# Startgate_Controller-Daughterboard.net
KiCad netlist of a schematic drawn in EAGLE
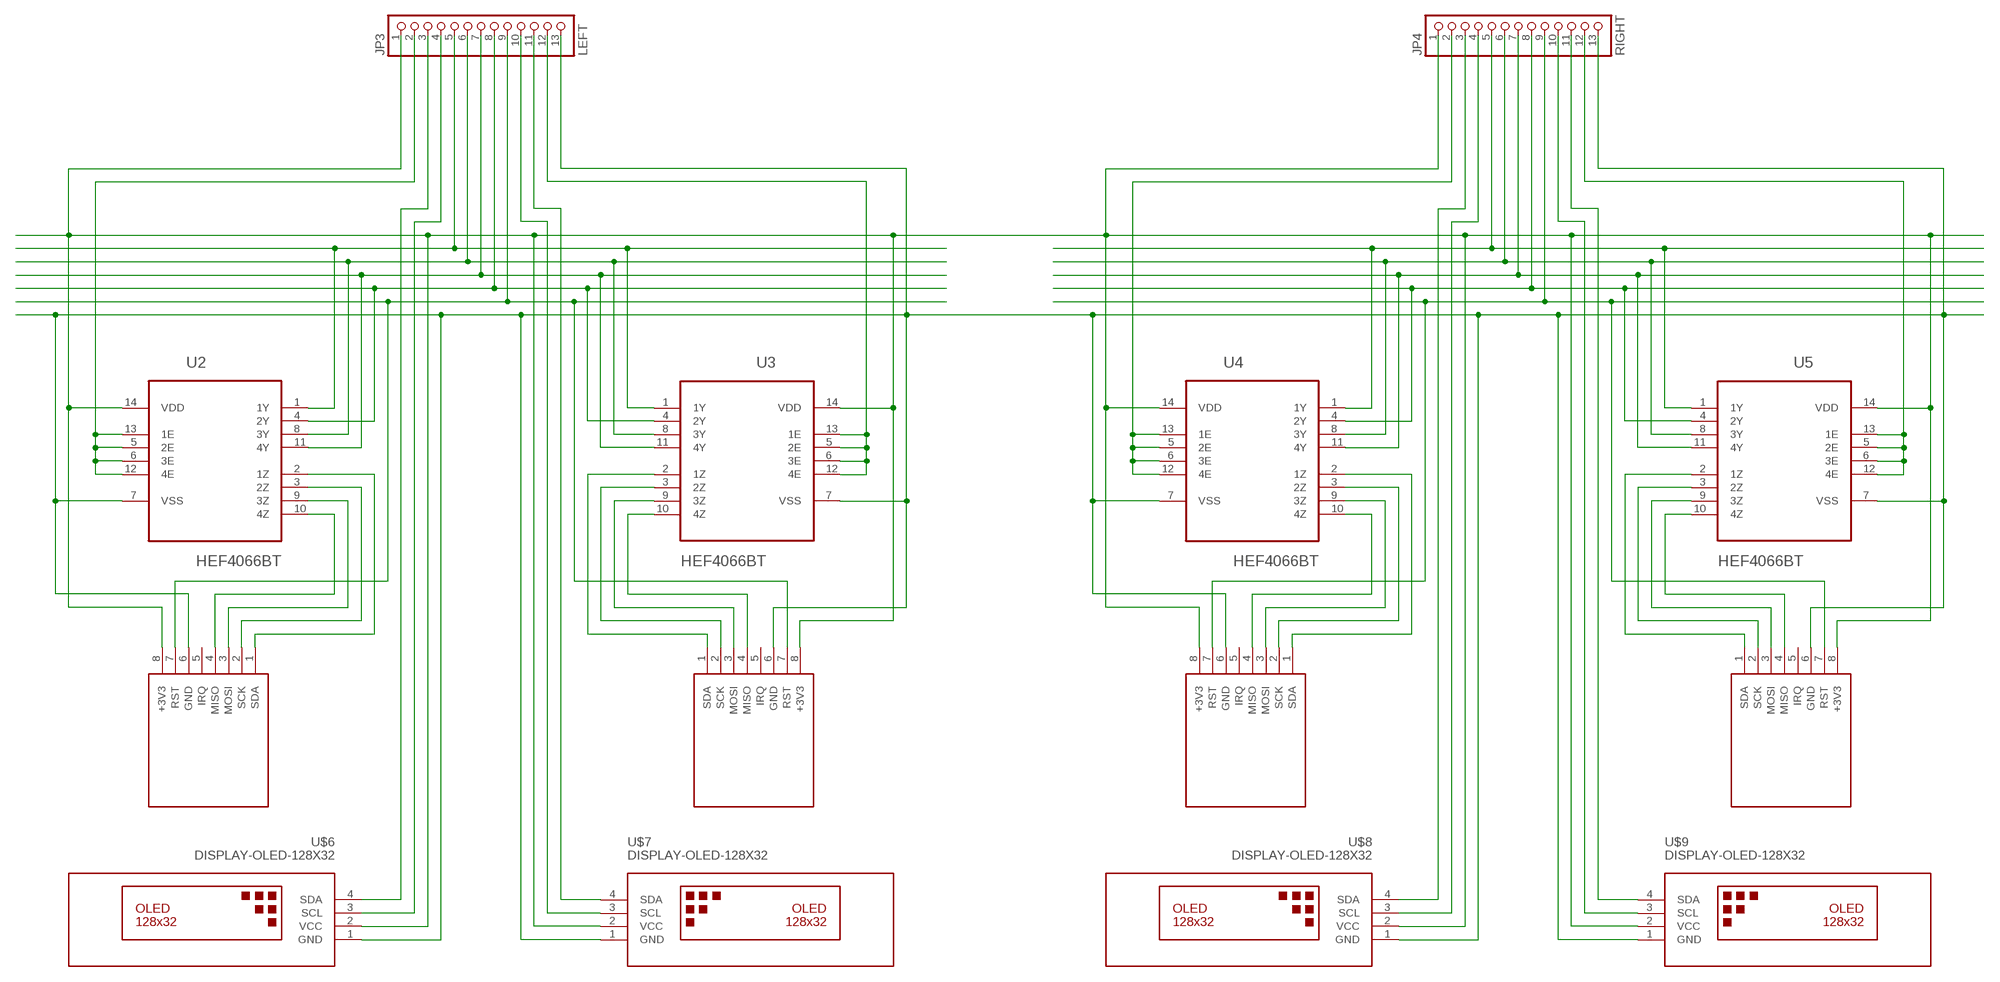
[diagram p0: schematic, sheet 1]

(export (version "E")
  (design (tool "Eeschema 10.0.6"))
  (components
    (comp (ref "JP3")
      (value "LEFT")
      (footprint "eagle-import:1X13")
      (libsource (lib "eagle-import") (part "PINHD-1X13"))
    )
    (comp (ref "JP4")
      (value "RIGHT")
      (footprint "eagle-import:1X13")
      (libsource (lib "eagle-import") (part "PINHD-1X13"))
    )
    (comp (ref "U$2")
      (value "RFID-RC522")
      (footprint "eagle-import:RFID-RC522")
      (libsource (lib "eagle-import") (part "RFID-RC522"))
    )
    (comp (ref "U$3")
      (value "RFID-RC522")
      (footprint "eagle-import:RFID-RC522")
      (libsource (lib "eagle-import") (part "RFID-RC522"))
    )
    (comp (ref "U$4")
      (value "RFID-RC522")
      (footprint "eagle-import:RFID-RC522")
      (libsource (lib "eagle-import") (part "RFID-RC522"))
    )
    (comp (ref "U$5")
      (value "RFID-RC522")
      (footprint "eagle-import:RFID-RC522")
      (libsource (lib "eagle-import") (part "RFID-RC522"))
    )
    (comp (ref "U$6")
      (value "DISPLAY-OLED-128X32")
      (footprint "eagle-import:DISPLAY-OLED-128X32")
      (libsource (lib "eagle-import") (part "DISPLAY-OLED-128X32"))
    )
    (comp (ref "U$7")
      (value "DISPLAY-OLED-128X32")
      (footprint "eagle-import:DISPLAY-OLED-128X32")
      (libsource (lib "eagle-import") (part "DISPLAY-OLED-128X32"))
    )
    (comp (ref "U$8")
      (value "DISPLAY-OLED-128X32")
      (footprint "eagle-import:DISPLAY-OLED-128X32")
      (libsource (lib "eagle-import") (part "DISPLAY-OLED-128X32"))
    )
    (comp (ref "U$9")
      (value "DISPLAY-OLED-128X32")
      (footprint "eagle-import:DISPLAY-OLED-128X32")
      (libsource (lib "eagle-import") (part "DISPLAY-OLED-128X32"))
    )
    (comp (ref "U2")
      (value "HEF4066BT")
      (footprint "eagle-import:SOIC127P600X175-14N")
      (libsource (lib "eagle-import") (part "HEF4066BT"))
    )
    (comp (ref "U3")
      (value "HEF4066BT")
      (footprint "eagle-import:SOIC127P600X175-14N")
      (libsource (lib "eagle-import") (part "HEF4066BT"))
    )
    (comp (ref "U4")
      (value "HEF4066BT")
      (footprint "eagle-import:SOIC127P600X175-14N")
      (libsource (lib "eagle-import") (part "HEF4066BT"))
    )
    (comp (ref "U5")
      (value "HEF4066BT")
      (footprint "eagle-import:SOIC127P600X175-14N")
      (libsource (lib "eagle-import") (part "HEF4066BT"))
    )
  )
  (nets
    (net (code "1") (name "Net-(U$2-+3V3)") (class "Default")
      (node (ref "JP3") (pin "1") (pinfunction "1_1") (pintype "passive"))
      (node (ref "JP4") (pin "1") (pinfunction "1_1") (pintype "passive"))
      (node (ref "U$2") (pin "8") (pinfunction "+3V3_8") (pintype "power_in"))
      (node (ref "U$3") (pin "8") (pinfunction "+3V3_8") (pintype "power_in"))
      (node (ref "U$4") (pin "8") (pinfunction "+3V3_8") (pintype "power_in"))
      (node (ref "U$5") (pin "8") (pinfunction "+3V3_8") (pintype "power_in"))
      (node (ref "U$6") (pin "2") (pinfunction "VCC_2") (pintype "power_in"))
      (node (ref "U$7") (pin "2") (pinfunction "VCC_2") (pintype "power_in"))
      (node (ref "U$8") (pin "2") (pinfunction "VCC_2") (pintype "power_in"))
      (node (ref "U$9") (pin "2") (pinfunction "VCC_2") (pintype "power_in"))
      (node (ref "U2") (pin "14") (pinfunction "VDD_14") (pintype "power_in"))
      (node (ref "U3") (pin "14") (pinfunction "VDD_14") (pintype "power_in"))
      (node (ref "U4") (pin "14") (pinfunction "VDD_14") (pintype "power_in"))
      (node (ref "U5") (pin "14") (pinfunction "VDD_14") (pintype "power_in"))
    )
    (net (code "2") (name "Net-(U$2-GND)") (class "Default")
      (node (ref "JP3") (pin "13") (pinfunction "13_13") (pintype "passive"))
      (node (ref "JP4") (pin "13") (pinfunction "13_13") (pintype "passive"))
      (node (ref "U$2") (pin "6") (pinfunction "GND_6") (pintype "power_in"))
      (node (ref "U$3") (pin "6") (pinfunction "GND_6") (pintype "power_in"))
      (node (ref "U$4") (pin "6") (pinfunction "GND_6") (pintype "power_in"))
      (node (ref "U$5") (pin "6") (pinfunction "GND_6") (pintype "power_in"))
      (node (ref "U$6") (pin "1") (pinfunction "GND_1") (pintype "power_in"))
      (node (ref "U$7") (pin "1") (pinfunction "GND_1") (pintype "power_in"))
      (node (ref "U$8") (pin "1") (pinfunction "GND_1") (pintype "power_in"))
      (node (ref "U$9") (pin "1") (pinfunction "GND_1") (pintype "power_in"))
      (node (ref "U2") (pin "7") (pinfunction "VSS_7") (pintype "passive"))
      (node (ref "U3") (pin "7") (pinfunction "VSS_7") (pintype "passive"))
      (node (ref "U4") (pin "7") (pinfunction "VSS_7") (pintype "passive"))
      (node (ref "U5") (pin "7") (pinfunction "VSS_7") (pintype "passive"))
    )
    (net (code "3") (name "Net-(U$2-MISO)") (class "Default")
      (node (ref "U$2") (pin "4") (pinfunction "MISO_4") (pintype "bidirectional"))
      (node (ref "U2") (pin "10") (pinfunction "4Z_10") (pintype "bidirectional"))
    )
    (net (code "4") (name "Net-(U$2-MOSI)") (class "Default")
      (node (ref "U$2") (pin "3") (pinfunction "MOSI_3") (pintype "bidirectional"))
      (node (ref "U2") (pin "9") (pinfunction "3Z_9") (pintype "bidirectional"))
    )
    (net (code "5") (name "Net-(U$2-RST)") (class "Default")
      (node (ref "JP3") (pin "9") (pinfunction "9_9") (pintype "passive"))
      (node (ref "U$2") (pin "7") (pinfunction "RST_7") (pintype "bidirectional"))
      (node (ref "U$3") (pin "7") (pinfunction "RST_7") (pintype "bidirectional"))
    )
    (net (code "6") (name "Net-(U$2-SCK)") (class "Default")
      (node (ref "U$2") (pin "2") (pinfunction "SCK_2") (pintype "bidirectional"))
      (node (ref "U2") (pin "3") (pinfunction "2Z_3") (pintype "bidirectional"))
    )
    (net (code "7") (name "Net-(U$2-SDA)") (class "Default")
      (node (ref "U$2") (pin "1") (pinfunction "SDA_1") (pintype "bidirectional"))
      (node (ref "U2") (pin "2") (pinfunction "1Z_2") (pintype "bidirectional"))
    )
    (net (code "8") (name "Net-(U$3-MISO)") (class "Default")
      (node (ref "U$3") (pin "4") (pinfunction "MISO_4") (pintype "bidirectional"))
      (node (ref "U3") (pin "10") (pinfunction "4Z_10") (pintype "bidirectional"))
    )
    (net (code "9") (name "Net-(U$3-MOSI)") (class "Default")
      (node (ref "U$3") (pin "3") (pinfunction "MOSI_3") (pintype "bidirectional"))
      (node (ref "U3") (pin "9") (pinfunction "3Z_9") (pintype "bidirectional"))
    )
    (net (code "10") (name "Net-(U$3-SCK)") (class "Default")
      (node (ref "U$3") (pin "2") (pinfunction "SCK_2") (pintype "bidirectional"))
      (node (ref "U3") (pin "3") (pinfunction "2Z_3") (pintype "bidirectional"))
    )
    (net (code "11") (name "Net-(U$3-SDA)") (class "Default")
      (node (ref "U$3") (pin "1") (pinfunction "SDA_1") (pintype "bidirectional"))
      (node (ref "U3") (pin "2") (pinfunction "1Z_2") (pintype "bidirectional"))
    )
    (net (code "12") (name "Net-(U$4-MISO)") (class "Default")
      (node (ref "U$4") (pin "4") (pinfunction "MISO_4") (pintype "bidirectional"))
      (node (ref "U4") (pin "10") (pinfunction "4Z_10") (pintype "bidirectional"))
    )
    (net (code "13") (name "Net-(U$4-MOSI)") (class "Default")
      (node (ref "U$4") (pin "3") (pinfunction "MOSI_3") (pintype "bidirectional"))
      (node (ref "U4") (pin "9") (pinfunction "3Z_9") (pintype "bidirectional"))
    )
    (net (code "14") (name "Net-(U$4-RST)") (class "Default")
      (node (ref "JP4") (pin "9") (pinfunction "9_9") (pintype "passive"))
      (node (ref "U$4") (pin "7") (pinfunction "RST_7") (pintype "bidirectional"))
      (node (ref "U$5") (pin "7") (pinfunction "RST_7") (pintype "bidirectional"))
    )
    (net (code "15") (name "Net-(U$4-SCK)") (class "Default")
      (node (ref "U$4") (pin "2") (pinfunction "SCK_2") (pintype "bidirectional"))
      (node (ref "U4") (pin "3") (pinfunction "2Z_3") (pintype "bidirectional"))
    )
    (net (code "16") (name "Net-(U$4-SDA)") (class "Default")
      (node (ref "U$4") (pin "1") (pinfunction "SDA_1") (pintype "bidirectional"))
      (node (ref "U4") (pin "2") (pinfunction "1Z_2") (pintype "bidirectional"))
    )
    (net (code "17") (name "Net-(U$5-MISO)") (class "Default")
      (node (ref "U$5") (pin "4") (pinfunction "MISO_4") (pintype "bidirectional"))
      (node (ref "U5") (pin "10") (pinfunction "4Z_10") (pintype "bidirectional"))
    )
    (net (code "18") (name "Net-(U$5-MOSI)") (class "Default")
      (node (ref "U$5") (pin "3") (pinfunction "MOSI_3") (pintype "bidirectional"))
      (node (ref "U5") (pin "9") (pinfunction "3Z_9") (pintype "bidirectional"))
    )
    (net (code "19") (name "Net-(U$5-SCK)") (class "Default")
      (node (ref "U$5") (pin "2") (pinfunction "SCK_2") (pintype "bidirectional"))
      (node (ref "U5") (pin "3") (pinfunction "2Z_3") (pintype "bidirectional"))
    )
    (net (code "20") (name "Net-(U$5-SDA)") (class "Default")
      (node (ref "U$5") (pin "1") (pinfunction "SDA_1") (pintype "bidirectional"))
      (node (ref "U5") (pin "2") (pinfunction "1Z_2") (pintype "bidirectional"))
    )
    (net (code "21") (name "Net-(U$6-SCL)") (class "Default")
      (node (ref "JP3") (pin "4") (pinfunction "4_4") (pintype "passive"))
      (node (ref "U$6") (pin "3") (pinfunction "SCL_3") (pintype "bidirectional"))
    )
    (net (code "22") (name "Net-(U$6-SDA)") (class "Default")
      (node (ref "JP3") (pin "3") (pinfunction "3_3") (pintype "passive"))
      (node (ref "U$6") (pin "4") (pinfunction "SDA_4") (pintype "bidirectional"))
    )
    (net (code "23") (name "Net-(U$7-SCL)") (class "Default")
      (node (ref "JP3") (pin "10") (pinfunction "10_10") (pintype "passive"))
      (node (ref "U$7") (pin "3") (pinfunction "SCL_3") (pintype "bidirectional"))
    )
    (net (code "24") (name "Net-(U$7-SDA)") (class "Default")
      (node (ref "JP3") (pin "11") (pinfunction "11_11") (pintype "passive"))
      (node (ref "U$7") (pin "4") (pinfunction "SDA_4") (pintype "bidirectional"))
    )
    (net (code "25") (name "Net-(U$8-SCL)") (class "Default")
      (node (ref "JP4") (pin "4") (pinfunction "4_4") (pintype "passive"))
      (node (ref "U$8") (pin "3") (pinfunction "SCL_3") (pintype "bidirectional"))
    )
    (net (code "26") (name "Net-(U$8-SDA)") (class "Default")
      (node (ref "JP4") (pin "3") (pinfunction "3_3") (pintype "passive"))
      (node (ref "U$8") (pin "4") (pinfunction "SDA_4") (pintype "bidirectional"))
    )
    (net (code "27") (name "Net-(U$9-SCL)") (class "Default")
      (node (ref "JP4") (pin "10") (pinfunction "10_10") (pintype "passive"))
      (node (ref "U$9") (pin "3") (pinfunction "SCL_3") (pintype "bidirectional"))
    )
    (net (code "28") (name "Net-(U$9-SDA)") (class "Default")
      (node (ref "JP4") (pin "11") (pinfunction "11_11") (pintype "passive"))
      (node (ref "U$9") (pin "4") (pinfunction "SDA_4") (pintype "bidirectional"))
    )
    (net (code "29") (name "Net-(U2-1E)") (class "Default")
      (node (ref "JP3") (pin "2") (pinfunction "2_2") (pintype "passive"))
      (node (ref "U2") (pin "12") (pinfunction "4E_12") (pintype "input"))
      (node (ref "U2") (pin "13") (pinfunction "1E_13") (pintype "input"))
      (node (ref "U2") (pin "5") (pinfunction "2E_5") (pintype "input"))
      (node (ref "U2") (pin "6") (pinfunction "3E_6") (pintype "input"))
    )
    (net (code "30") (name "Net-(U2-1Y)") (class "Default")
      (node (ref "JP3") (pin "5") (pinfunction "5_5") (pintype "passive"))
      (node (ref "U2") (pin "1") (pinfunction "1Y_1") (pintype "bidirectional"))
      (node (ref "U3") (pin "1") (pinfunction "1Y_1") (pintype "bidirectional"))
    )
    (net (code "31") (name "Net-(U2-2Y)") (class "Default")
      (node (ref "JP3") (pin "8") (pinfunction "8_8") (pintype "passive"))
      (node (ref "U2") (pin "4") (pinfunction "2Y_4") (pintype "bidirectional"))
      (node (ref "U3") (pin "4") (pinfunction "2Y_4") (pintype "bidirectional"))
    )
    (net (code "32") (name "Net-(U2-3Y)") (class "Default")
      (node (ref "JP3") (pin "6") (pinfunction "6_6") (pintype "passive"))
      (node (ref "U2") (pin "8") (pinfunction "3Y_8") (pintype "bidirectional"))
      (node (ref "U3") (pin "8") (pinfunction "3Y_8") (pintype "bidirectional"))
    )
    (net (code "33") (name "Net-(U2-4Y)") (class "Default")
      (node (ref "JP3") (pin "7") (pinfunction "7_7") (pintype "passive"))
      (node (ref "U2") (pin "11") (pinfunction "4Y_11") (pintype "bidirectional"))
      (node (ref "U3") (pin "11") (pinfunction "4Y_11") (pintype "bidirectional"))
    )
    (net (code "34") (name "Net-(U3-1E)") (class "Default")
      (node (ref "JP3") (pin "12") (pinfunction "12_12") (pintype "passive"))
      (node (ref "U3") (pin "12") (pinfunction "4E_12") (pintype "input"))
      (node (ref "U3") (pin "13") (pinfunction "1E_13") (pintype "input"))
      (node (ref "U3") (pin "5") (pinfunction "2E_5") (pintype "input"))
      (node (ref "U3") (pin "6") (pinfunction "3E_6") (pintype "input"))
    )
    (net (code "35") (name "Net-(U4-1E)") (class "Default")
      (node (ref "JP4") (pin "2") (pinfunction "2_2") (pintype "passive"))
      (node (ref "U4") (pin "12") (pinfunction "4E_12") (pintype "input"))
      (node (ref "U4") (pin "13") (pinfunction "1E_13") (pintype "input"))
      (node (ref "U4") (pin "5") (pinfunction "2E_5") (pintype "input"))
      (node (ref "U4") (pin "6") (pinfunction "3E_6") (pintype "input"))
    )
    (net (code "36") (name "Net-(U4-1Y)") (class "Default")
      (node (ref "JP4") (pin "5") (pinfunction "5_5") (pintype "passive"))
      (node (ref "U4") (pin "1") (pinfunction "1Y_1") (pintype "bidirectional"))
      (node (ref "U5") (pin "1") (pinfunction "1Y_1") (pintype "bidirectional"))
    )
    (net (code "37") (name "Net-(U4-2Y)") (class "Default")
      (node (ref "JP4") (pin "8") (pinfunction "8_8") (pintype "passive"))
      (node (ref "U4") (pin "4") (pinfunction "2Y_4") (pintype "bidirectional"))
      (node (ref "U5") (pin "4") (pinfunction "2Y_4") (pintype "bidirectional"))
    )
    (net (code "38") (name "Net-(U4-3Y)") (class "Default")
      (node (ref "JP4") (pin "6") (pinfunction "6_6") (pintype "passive"))
      (node (ref "U4") (pin "8") (pinfunction "3Y_8") (pintype "bidirectional"))
      (node (ref "U5") (pin "8") (pinfunction "3Y_8") (pintype "bidirectional"))
    )
    (net (code "39") (name "Net-(U4-4Y)") (class "Default")
      (node (ref "JP4") (pin "7") (pinfunction "7_7") (pintype "passive"))
      (node (ref "U4") (pin "11") (pinfunction "4Y_11") (pintype "bidirectional"))
      (node (ref "U5") (pin "11") (pinfunction "4Y_11") (pintype "bidirectional"))
    )
    (net (code "40") (name "Net-(U5-1E)") (class "Default")
      (node (ref "JP4") (pin "12") (pinfunction "12_12") (pintype "passive"))
      (node (ref "U5") (pin "12") (pinfunction "4E_12") (pintype "input"))
      (node (ref "U5") (pin "13") (pinfunction "1E_13") (pintype "input"))
      (node (ref "U5") (pin "5") (pinfunction "2E_5") (pintype "input"))
      (node (ref "U5") (pin "6") (pinfunction "3E_6") (pintype "input"))
    )
    (net (code "41") (name "unconnected-(U$2-IRQ-Pad5)") (class "Default")
      (node (ref "U$2") (pin "5") (pinfunction "IRQ_5") (pintype "bidirectional"))
    )
    (net (code "42") (name "unconnected-(U$3-IRQ-Pad5)") (class "Default")
      (node (ref "U$3") (pin "5") (pinfunction "IRQ_5") (pintype "bidirectional"))
    )
    (net (code "43") (name "unconnected-(U$4-IRQ-Pad5)") (class "Default")
      (node (ref "U$4") (pin "5") (pinfunction "IRQ_5") (pintype "bidirectional"))
    )
    (net (code "44") (name "unconnected-(U$5-IRQ-Pad5)") (class "Default")
      (node (ref "U$5") (pin "5") (pinfunction "IRQ_5") (pintype "bidirectional"))
    )
  )
)
